# sonar.net
KiCad netlist of a schematic drawn in Altium Designer
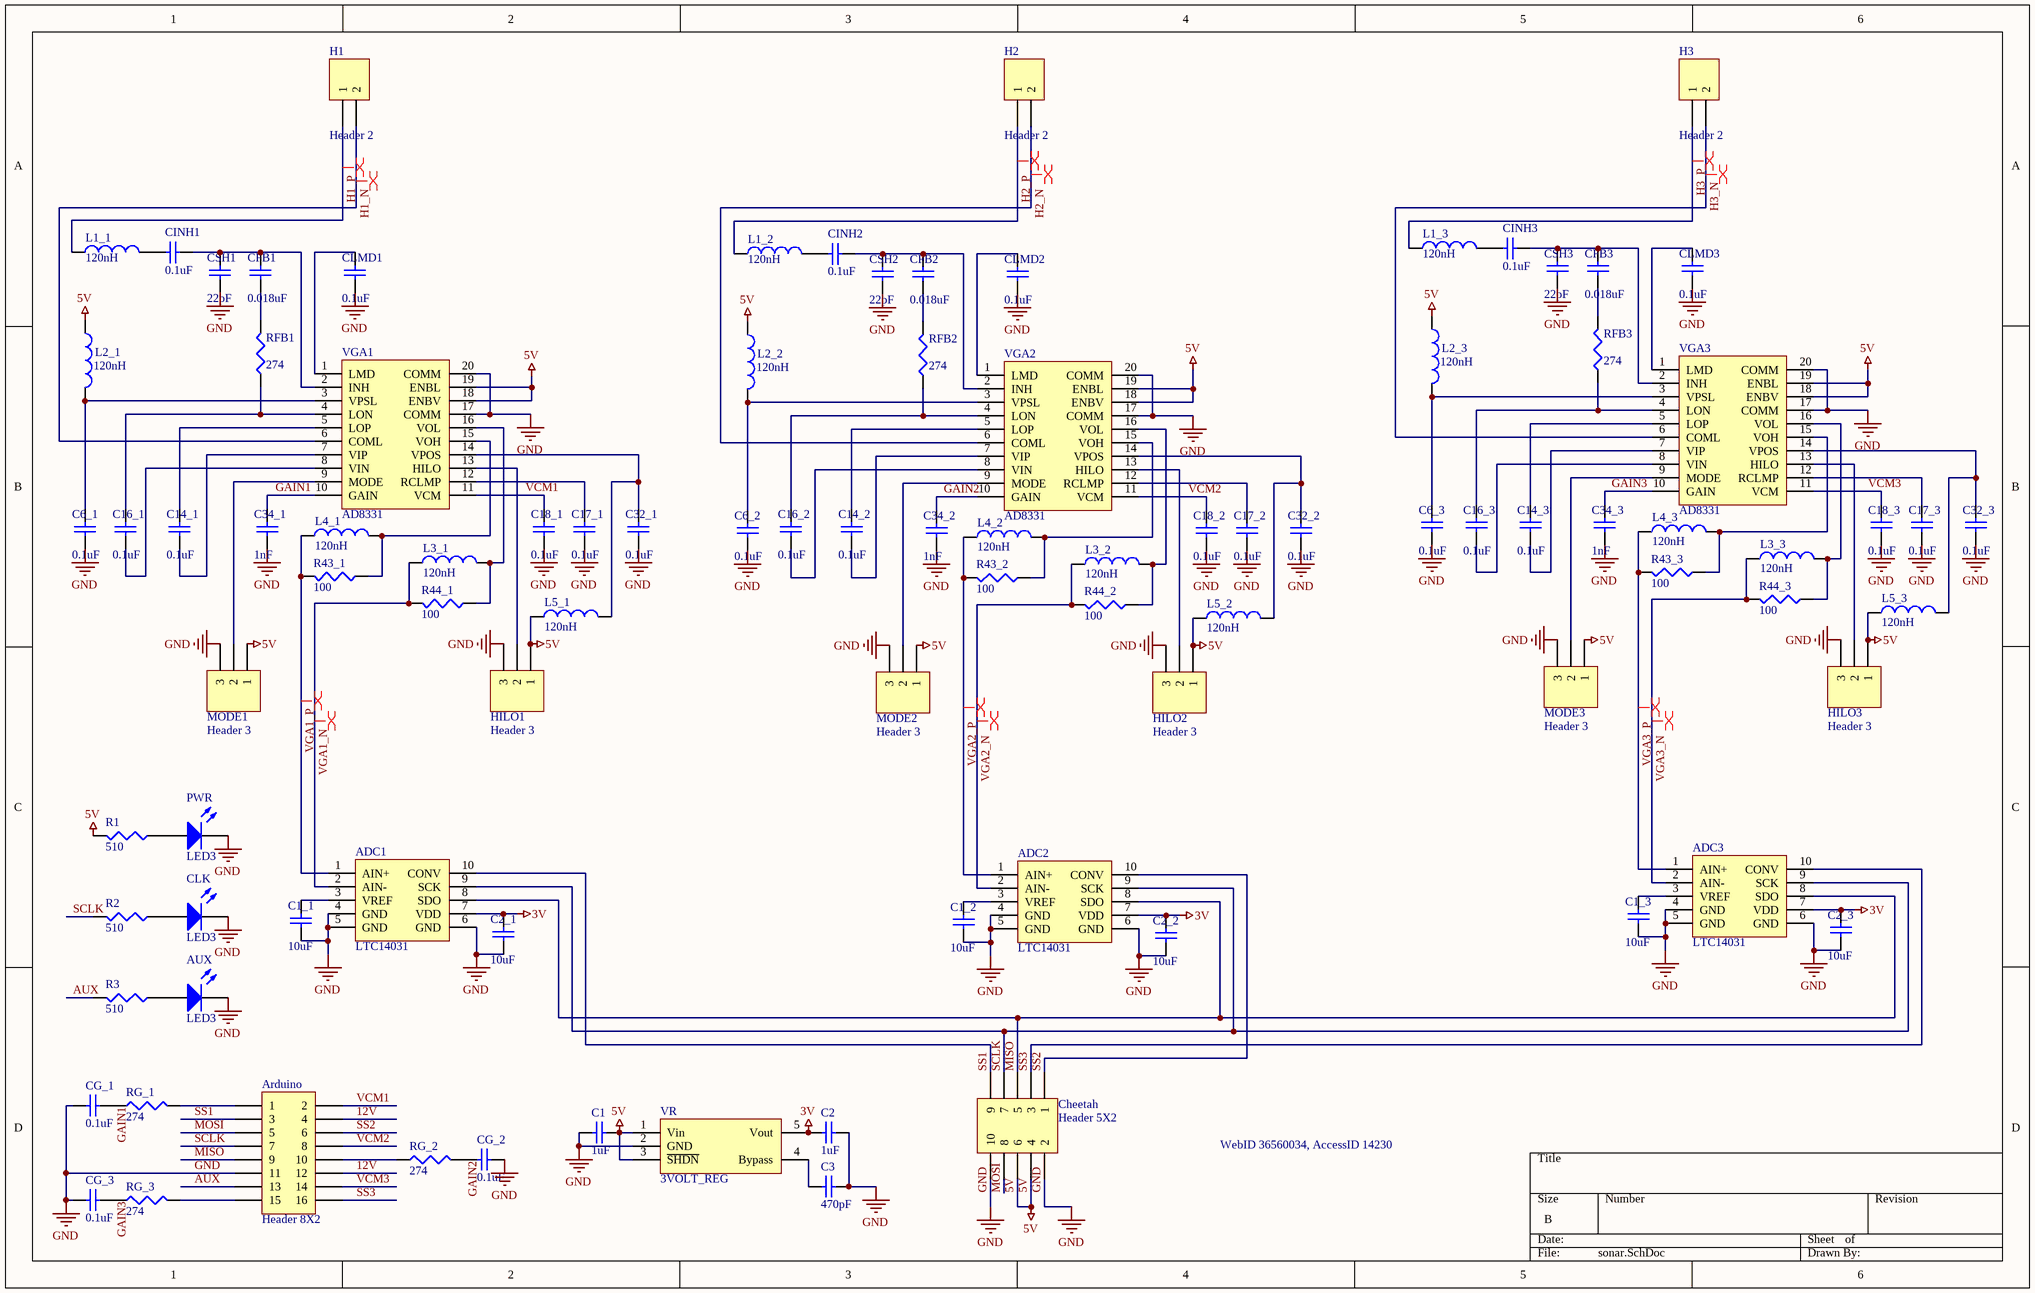
[diagram p0: sonar.SchDoc]

(export (version "E")
  (design (tool "Eeschema 10.0.6"))
  (components
    (comp (ref "ADC1") (value "LTC14031") (footprint "ADC") (libsource (lib "sonar") (part "ADC")))
    (comp (ref "ADC2") (value "LTC14031") (footprint "ADC") (libsource (lib "sonar") (part "ADC")))
    (comp (ref "ADC3") (value "LTC14031") (footprint "ADC") (libsource (lib "sonar") (part "ADC")))
    (comp (ref "Arduino")
      (value "Header 8X2")
      (footprint "HDR2X8")
      (description "Header, 8-Pin, Dual row")
      (fields (field (name "PUBLISHER") "Altium Limited"))
      (libsource (lib "Miscellaneous Connectors") (part "Header 8X2"))
    )
    (comp (ref "AUX")
      (value "LED3")
      (footprint "LED")
      (description "Typical BLUE SiC LED")
      (fields (field (name "PUBLISHER") "Altium Limited"))
      (libsource (lib "Miscellaneous Devices") (part "LED3"))
    )
    (comp (ref "C1")
      (value "1uF")
      (footprint "cap_vreg_1uf")
      (description "Capacitor")
      (fields (field (name "Comment") "Cap") (field (name "PUBLISHER") "Altium Limited"))
      (libsource (lib "Miscellaneous Devices") (part "Cap"))
    )
    (comp (ref "C1_1")
      (value "10uF")
      (footprint "cap_adc_10uf")
      (description "Capacitor")
      (fields (field (name "Comment") "Cap") (field (name "PUBLISHER") "Altium Limited"))
      (libsource (lib "Miscellaneous Devices") (part "Cap"))
    )
    (comp (ref "C1_2")
      (value "10uF")
      (footprint "cap_adc_10uf")
      (description "Capacitor")
      (fields (field (name "Comment") "Cap") (field (name "PUBLISHER") "Altium Limited"))
      (libsource (lib "Miscellaneous Devices") (part "Cap"))
    )
    (comp (ref "C1_3")
      (value "10uF")
      (footprint "cap_adc_10uf")
      (description "Capacitor")
      (fields (field (name "Comment") "Cap") (field (name "PUBLISHER") "Altium Limited"))
      (libsource (lib "Miscellaneous Devices") (part "Cap"))
    )
    (comp (ref "C2")
      (value "1uF")
      (footprint "cap_vreg_1uf")
      (description "Capacitor")
      (fields (field (name "Comment") "Cap") (field (name "PUBLISHER") "Altium Limited"))
      (libsource (lib "Miscellaneous Devices") (part "Cap"))
    )
    (comp (ref "C2_1")
      (value "10uF")
      (footprint "cap_adc_10uf")
      (description "Capacitor")
      (fields (field (name "Comment") "Cap") (field (name "PUBLISHER") "Altium Limited"))
      (libsource (lib "Miscellaneous Devices") (part "Cap"))
    )
    (comp (ref "C2_2")
      (value "10uF")
      (footprint "cap_adc_10uf")
      (description "Capacitor")
      (fields (field (name "Comment") "Cap") (field (name "PUBLISHER") "Altium Limited"))
      (libsource (lib "Miscellaneous Devices") (part "Cap"))
    )
    (comp (ref "C2_3")
      (value "10uF")
      (footprint "cap_adc_10uf")
      (description "Capacitor")
      (fields (field (name "Comment") "Cap") (field (name "PUBLISHER") "Altium Limited"))
      (libsource (lib "Miscellaneous Devices") (part "Cap"))
    )
    (comp (ref "C3")
      (value "470pF")
      (footprint "CAP_VREG_470PF")
      (description "Capacitor")
      (fields (field (name "Comment") "Cap") (field (name "PUBLISHER") "Altium Limited"))
      (libsource (lib "Miscellaneous Devices") (part "Cap"))
    )
    (comp (ref "C6_1")
      (value "0.1uF")
      (footprint "CAP_VGA_01UF")
      (description "Capacitor")
      (fields (field (name "Comment") "Cap") (field (name "PUBLISHER") "Altium Limited"))
      (libsource (lib "Miscellaneous Devices") (part "Cap"))
    )
    (comp (ref "C6_2")
      (value "0.1uF")
      (footprint "CAP_VGA_01UF")
      (description "Capacitor")
      (fields (field (name "Comment") "Cap") (field (name "PUBLISHER") "Altium Limited"))
      (libsource (lib "Miscellaneous Devices") (part "Cap"))
    )
    (comp (ref "C6_3")
      (value "0.1uF")
      (footprint "CAP_VGA_01UF")
      (description "Capacitor")
      (fields (field (name "Comment") "Cap") (field (name "PUBLISHER") "Altium Limited"))
      (libsource (lib "Miscellaneous Devices") (part "Cap"))
    )
    (comp (ref "C14_1")
      (value "0.1uF")
      (footprint "CAP_VGA_01UF")
      (description "Capacitor")
      (fields (field (name "Comment") "Cap") (field (name "PUBLISHER") "Altium Limited"))
      (libsource (lib "Miscellaneous Devices") (part "Cap"))
    )
    (comp (ref "C14_2")
      (value "0.1uF")
      (footprint "CAP_VGA_01UF")
      (description "Capacitor")
      (fields (field (name "Comment") "Cap") (field (name "PUBLISHER") "Altium Limited"))
      (libsource (lib "Miscellaneous Devices") (part "Cap"))
    )
    (comp (ref "C14_3")
      (value "0.1uF")
      (footprint "CAP_VGA_01UF")
      (description "Capacitor")
      (fields (field (name "Comment") "Cap") (field (name "PUBLISHER") "Altium Limited"))
      (libsource (lib "Miscellaneous Devices") (part "Cap"))
    )
    (comp (ref "C16_1")
      (value "0.1uF")
      (footprint "CAP_VGA_01UF")
      (description "Capacitor")
      (fields (field (name "Comment") "Cap") (field (name "PUBLISHER") "Altium Limited"))
      (libsource (lib "Miscellaneous Devices") (part "Cap"))
    )
    (comp (ref "C16_2")
      (value "0.1uF")
      (footprint "CAP_VGA_01UF")
      (description "Capacitor")
      (fields (field (name "Comment") "Cap") (field (name "PUBLISHER") "Altium Limited"))
      (libsource (lib "Miscellaneous Devices") (part "Cap"))
    )
    (comp (ref "C16_3")
      (value "0.1uF")
      (footprint "CAP_VGA_01UF")
      (description "Capacitor")
      (fields (field (name "Comment") "Cap") (field (name "PUBLISHER") "Altium Limited"))
      (libsource (lib "Miscellaneous Devices") (part "Cap"))
    )
    (comp (ref "C17_1")
      (value "0.1uF")
      (footprint "CAP_VGA_01UF")
      (description "Capacitor")
      (fields (field (name "Comment") "Cap") (field (name "PUBLISHER") "Altium Limited"))
      (libsource (lib "Miscellaneous Devices") (part "Cap"))
    )
    (comp (ref "C17_2")
      (value "0.1uF")
      (footprint "CAP_VGA_01UF")
      (description "Capacitor")
      (fields (field (name "Comment") "Cap") (field (name "PUBLISHER") "Altium Limited"))
      (libsource (lib "Miscellaneous Devices") (part "Cap"))
    )
    (comp (ref "C17_3")
      (value "0.1uF")
      (footprint "CAP_VGA_01UF")
      (description "Capacitor")
      (fields (field (name "Comment") "Cap") (field (name "PUBLISHER") "Altium Limited"))
      (libsource (lib "Miscellaneous Devices") (part "Cap"))
    )
    (comp (ref "C18_1")
      (value "0.1uF")
      (footprint "CAP_VGA_01UF")
      (description "Capacitor")
      (fields (field (name "Comment") "Cap") (field (name "PUBLISHER") "Altium Limited"))
      (libsource (lib "Miscellaneous Devices") (part "Cap"))
    )
    (comp (ref "C18_2")
      (value "0.1uF")
      (footprint "CAP_VGA_01UF")
      (description "Capacitor")
      (fields (field (name "Comment") "Cap") (field (name "PUBLISHER") "Altium Limited"))
      (libsource (lib "Miscellaneous Devices") (part "Cap"))
    )
    (comp (ref "C18_3")
      (value "0.1uF")
      (footprint "CAP_VGA_01UF")
      (description "Capacitor")
      (fields (field (name "Comment") "Cap") (field (name "PUBLISHER") "Altium Limited"))
      (libsource (lib "Miscellaneous Devices") (part "Cap"))
    )
    (comp (ref "C32_1")
      (value "0.1uF")
      (footprint "CAP_VGA_01UF")
      (description "Capacitor")
      (fields (field (name "Comment") "Cap") (field (name "PUBLISHER") "Altium Limited"))
      (libsource (lib "Miscellaneous Devices") (part "Cap"))
    )
    (comp (ref "C32_2")
      (value "0.1uF")
      (footprint "CAP_VGA_01UF")
      (description "Capacitor")
      (fields (field (name "Comment") "Cap") (field (name "PUBLISHER") "Altium Limited"))
      (libsource (lib "Miscellaneous Devices") (part "Cap"))
    )
    (comp (ref "C32_3")
      (value "0.1uF")
      (footprint "CAP_VGA_01UF")
      (description "Capacitor")
      (fields (field (name "Comment") "Cap") (field (name "PUBLISHER") "Altium Limited"))
      (libsource (lib "Miscellaneous Devices") (part "Cap"))
    )
    (comp (ref "C34_1")
      (value "1nF")
      (footprint "CAP_VGA_01UF")
      (description "Capacitor")
      (fields (field (name "Comment") "Cap") (field (name "PUBLISHER") "Altium Limited"))
      (libsource (lib "Miscellaneous Devices") (part "Cap"))
    )
    (comp (ref "C34_2")
      (value "1nF")
      (footprint "CAP_VGA_01UF")
      (description "Capacitor")
      (fields (field (name "Comment") "Cap") (field (name "PUBLISHER") "Altium Limited"))
      (libsource (lib "Miscellaneous Devices") (part "Cap"))
    )
    (comp (ref "C34_3")
      (value "1nF")
      (footprint "CAP_VGA_01UF")
      (description "Capacitor")
      (fields (field (name "Comment") "Cap") (field (name "PUBLISHER") "Altium Limited"))
      (libsource (lib "Miscellaneous Devices") (part "Cap"))
    )
    (comp (ref "CFB1")
      (value "0.018uF")
      (footprint "CAP_VGA_01UF")
      (description "Capacitor")
      (fields (field (name "Comment") "Cap") (field (name "PUBLISHER") "Altium Limited"))
      (libsource (lib "Miscellaneous Devices") (part "Cap"))
    )
    (comp (ref "CFB2")
      (value "0.018uF")
      (footprint "CAP_VGA_01UF")
      (description "Capacitor")
      (fields (field (name "Comment") "Cap") (field (name "PUBLISHER") "Altium Limited"))
      (libsource (lib "Miscellaneous Devices") (part "Cap"))
    )
    (comp (ref "CFB3")
      (value "0.018uF")
      (footprint "CAP_VGA_01UF")
      (description "Capacitor")
      (fields (field (name "Comment") "Cap") (field (name "PUBLISHER") "Altium Limited"))
      (libsource (lib "Miscellaneous Devices") (part "Cap"))
    )
    (comp (ref "CG_1")
      (value "0.1uF")
      (footprint "CAP_VGA_01UF")
      (description "Capacitor")
      (fields (field (name "Comment") "Cap") (field (name "PUBLISHER") "Altium Limited"))
      (libsource (lib "Miscellaneous Devices") (part "Cap"))
    )
    (comp (ref "CG_2")
      (value "0.1uF")
      (footprint "CAP_VGA_01UF")
      (description "Capacitor")
      (fields (field (name "Comment") "Cap") (field (name "PUBLISHER") "Altium Limited"))
      (libsource (lib "Miscellaneous Devices") (part "Cap"))
    )
    (comp (ref "CG_3")
      (value "0.1uF")
      (footprint "CAP_VGA_01UF")
      (description "Capacitor")
      (fields (field (name "Comment") "Cap") (field (name "PUBLISHER") "Altium Limited"))
      (libsource (lib "Miscellaneous Devices") (part "Cap"))
    )
    (comp (ref "Cheetah")
      (value "Header 5X2")
      (footprint "HDR2X5")
      (description "Header, 5-Pin, Dual row")
      (fields (field (name "PUBLISHER") "Altium Limited"))
      (libsource (lib "Miscellaneous Connectors") (part "Header 5X2"))
    )
    (comp (ref "CINH1")
      (value "0.1uF")
      (footprint "CAP_VGA_01UF")
      (description "Capacitor")
      (fields (field (name "Comment") "Cap") (field (name "PUBLISHER") "Altium Limited"))
      (libsource (lib "Miscellaneous Devices") (part "Cap"))
    )
    (comp (ref "CINH2")
      (value "0.1uF")
      (footprint "CAP_VGA_01UF")
      (description "Capacitor")
      (fields (field (name "Comment") "Cap") (field (name "PUBLISHER") "Altium Limited"))
      (libsource (lib "Miscellaneous Devices") (part "Cap"))
    )
    (comp (ref "CINH3")
      (value "0.1uF")
      (footprint "CAP_VGA_01UF")
      (description "Capacitor")
      (fields (field (name "Comment") "Cap") (field (name "PUBLISHER") "Altium Limited"))
      (libsource (lib "Miscellaneous Devices") (part "Cap"))
    )
    (comp (ref "CLK")
      (value "LED3")
      (footprint "LED")
      (description "Typical BLUE SiC LED")
      (fields (field (name "PUBLISHER") "Altium Limited"))
      (libsource (lib "Miscellaneous Devices") (part "LED3"))
    )
    (comp (ref "CLMD1")
      (value "0.1uF")
      (footprint "CAP_VGA_01UF")
      (description "Capacitor")
      (fields (field (name "Comment") "Cap") (field (name "PUBLISHER") "Altium Limited"))
      (libsource (lib "Miscellaneous Devices") (part "Cap"))
    )
    (comp (ref "CLMD2")
      (value "0.1uF")
      (footprint "CAP_VGA_01UF")
      (description "Capacitor")
      (fields (field (name "Comment") "Cap") (field (name "PUBLISHER") "Altium Limited"))
      (libsource (lib "Miscellaneous Devices") (part "Cap"))
    )
    (comp (ref "CLMD3")
      (value "0.1uF")
      (footprint "CAP_VGA_01UF")
      (description "Capacitor")
      (fields (field (name "Comment") "Cap") (field (name "PUBLISHER") "Altium Limited"))
      (libsource (lib "Miscellaneous Devices") (part "Cap"))
    )
    (comp (ref "CSH1")
      (value "22pF")
      (footprint "CAP_VGA_01UF")
      (description "Capacitor")
      (fields (field (name "Comment") "Cap") (field (name "PUBLISHER") "Altium Limited"))
      (libsource (lib "Miscellaneous Devices") (part "Cap"))
    )
    (comp (ref "CSH2")
      (value "22pF")
      (footprint "CAP_VGA_01UF")
      (description "Capacitor")
      (fields (field (name "Comment") "Cap") (field (name "PUBLISHER") "Altium Limited"))
      (libsource (lib "Miscellaneous Devices") (part "Cap"))
    )
    (comp (ref "CSH3")
      (value "22pF")
      (footprint "CAP_VGA_01UF")
      (description "Capacitor")
      (fields (field (name "Comment") "Cap") (field (name "PUBLISHER") "Altium Limited"))
      (libsource (lib "Miscellaneous Devices") (part "Cap"))
    )
    (comp (ref "H1")
      (value "Header 2")
      (footprint "bnc")
      (description "Header, 2-Pin")
      (fields (field (name "PUBLISHER") "Altium Limited"))
      (libsource (lib "Miscellaneous Connectors") (part "Header 2"))
    )
    (comp (ref "H2")
      (value "Header 2")
      (footprint "bnc")
      (description "Header, 2-Pin")
      (fields (field (name "PUBLISHER") "Altium Limited"))
      (libsource (lib "Miscellaneous Connectors") (part "Header 2"))
    )
    (comp (ref "H3")
      (value "Header 2")
      (footprint "bnc")
      (description "Header, 2-Pin")
      (fields (field (name "PUBLISHER") "Altium Limited"))
      (libsource (lib "Miscellaneous Connectors") (part "Header 2"))
    )
    (comp (ref "HILO1")
      (value "Header 3")
      (footprint "HDR1X3")
      (description "Header, 3-Pin")
      (fields (field (name "PUBLISHER") "Altium Limited"))
      (libsource (lib "Miscellaneous Connectors") (part "Header 3"))
    )
    (comp (ref "HILO2")
      (value "Header 3")
      (footprint "HDR1X3")
      (description "Header, 3-Pin")
      (fields (field (name "PUBLISHER") "Altium Limited"))
      (libsource (lib "Miscellaneous Connectors") (part "Header 3"))
    )
    (comp (ref "HILO3")
      (value "Header 3")
      (footprint "HDR1X3")
      (description "Header, 3-Pin")
      (fields (field (name "PUBLISHER") "Altium Limited"))
      (libsource (lib "Miscellaneous Connectors") (part "Header 3"))
    )
    (comp (ref "L1_1")
      (value "120nH")
      (footprint "ind_vga_120nh")
      (description "Inductor")
      (fields (field (name "Comment") "FB Inductor") (field (name "PUBLISHER") "Altium Limited"))
      (libsource (lib "Miscellaneous Devices") (part "Inductor"))
    )
    (comp (ref "L1_2")
      (value "120nH")
      (footprint "ind_vga_120nh")
      (description "Inductor")
      (fields (field (name "Comment") "FB Inductor") (field (name "PUBLISHER") "Altium Limited"))
      (libsource (lib "Miscellaneous Devices") (part "Inductor"))
    )
    (comp (ref "L1_3")
      (value "120nH")
      (footprint "ind_vga_120nh")
      (description "Inductor")
      (fields (field (name "Comment") "FB Inductor") (field (name "PUBLISHER") "Altium Limited"))
      (libsource (lib "Miscellaneous Devices") (part "Inductor"))
    )
    (comp (ref "L2_1")
      (value "120nH")
      (footprint "ind_vga_120nh")
      (description "Inductor")
      (fields (field (name "Comment") "FB Inductor") (field (name "PUBLISHER") "Altium Limited"))
      (libsource (lib "Miscellaneous Devices") (part "Inductor"))
    )
    (comp (ref "L2_2")
      (value "120nH")
      (footprint "ind_vga_120nh")
      (description "Inductor")
      (fields (field (name "Comment") "FB Inductor") (field (name "PUBLISHER") "Altium Limited"))
      (libsource (lib "Miscellaneous Devices") (part "Inductor"))
    )
    (comp (ref "L2_3")
      (value "120nH")
      (footprint "ind_vga_120nh")
      (description "Inductor")
      (fields (field (name "Comment") "FB Inductor") (field (name "PUBLISHER") "Altium Limited"))
      (libsource (lib "Miscellaneous Devices") (part "Inductor"))
    )
    (comp (ref "L3_1")
      (value "120nH")
      (footprint "ind_vga_120nh")
      (description "Inductor")
      (fields (field (name "Comment") "FB Inductor") (field (name "PUBLISHER") "Altium Limited"))
      (libsource (lib "Miscellaneous Devices") (part "Inductor"))
    )
    (comp (ref "L3_2")
      (value "120nH")
      (footprint "ind_vga_120nh")
      (description "Inductor")
      (fields (field (name "Comment") "FB Inductor") (field (name "PUBLISHER") "Altium Limited"))
      (libsource (lib "Miscellaneous Devices") (part "Inductor"))
    )
    (comp (ref "L3_3")
      (value "120nH")
      (footprint "ind_vga_120nh")
      (description "Inductor")
      (fields (field (name "Comment") "FB Inductor") (field (name "PUBLISHER") "Altium Limited"))
      (libsource (lib "Miscellaneous Devices") (part "Inductor"))
    )
    (comp (ref "L4_1")
      (value "120nH")
      (footprint "ind_vga_120nh")
      (description "Inductor")
      (fields (field (name "Comment") "FB Inductor") (field (name "PUBLISHER") "Altium Limited"))
      (libsource (lib "Miscellaneous Devices") (part "Inductor"))
    )
    (comp (ref "L4_2")
      (value "120nH")
      (footprint "ind_vga_120nh")
      (description "Inductor")
      (fields (field (name "Comment") "FB Inductor") (field (name "PUBLISHER") "Altium Limited"))
      (libsource (lib "Miscellaneous Devices") (part "Inductor"))
    )
    (comp (ref "L4_3")
      (value "120nH")
      (footprint "ind_vga_120nh")
      (description "Inductor")
      (fields (field (name "Comment") "FB Inductor") (field (name "PUBLISHER") "Altium Limited"))
      (libsource (lib "Miscellaneous Devices") (part "Inductor"))
    )
    (comp (ref "L5_1")
      (value "120nH")
      (footprint "ind_vga_120nh")
      (description "Inductor")
      (fields (field (name "Comment") "FB Inductor") (field (name "PUBLISHER") "Altium Limited"))
      (libsource (lib "Miscellaneous Devices") (part "Inductor"))
    )
    (comp (ref "L5_2")
      (value "120nH")
      (footprint "ind_vga_120nh")
      (description "Inductor")
      (fields (field (name "Comment") "FB Inductor") (field (name "PUBLISHER") "Altium Limited"))
      (libsource (lib "Miscellaneous Devices") (part "Inductor"))
    )
    (comp (ref "L5_3")
      (value "120nH")
      (footprint "ind_vga_120nh")
      (description "Inductor")
      (fields (field (name "Comment") "FB Inductor") (field (name "PUBLISHER") "Altium Limited"))
      (libsource (lib "Miscellaneous Devices") (part "Inductor"))
    )
    (comp (ref "MODE1")
      (value "Header 3")
      (footprint "HDR1X3")
      (description "Header, 3-Pin")
      (fields (field (name "PUBLISHER") "Altium Limited"))
      (libsource (lib "Miscellaneous Connectors") (part "Header 3"))
    )
    (comp (ref "MODE2")
      (value "Header 3")
      (footprint "HDR1X3")
      (description "Header, 3-Pin")
      (fields (field (name "PUBLISHER") "Altium Limited"))
      (libsource (lib "Miscellaneous Connectors") (part "Header 3"))
    )
    (comp (ref "MODE3")
      (value "Header 3")
      (footprint "HDR1X3")
      (description "Header, 3-Pin")
      (fields (field (name "PUBLISHER") "Altium Limited"))
      (libsource (lib "Miscellaneous Connectors") (part "Header 3"))
    )
    (comp (ref "PWR")
      (value "LED3")
      (footprint "LED")
      (description "Typical BLUE SiC LED")
      (fields (field (name "PUBLISHER") "Altium Limited"))
      (libsource (lib "Miscellaneous Devices") (part "LED3"))
    )
    (comp (ref "R1")
      (value "510")
      (footprint "res_vga_274")
      (description "Resistor")
      (fields (field (name "Comment") "Res3") (field (name "PUBLISHER") "Altium Limited"))
      (libsource (lib "Miscellaneous Devices") (part "Res3"))
    )
    (comp (ref "R2")
      (value "510")
      (footprint "res_vga_274")
      (description "Resistor")
      (fields (field (name "Comment") "Res3") (field (name "PUBLISHER") "Altium Limited"))
      (libsource (lib "Miscellaneous Devices") (part "Res3"))
    )
    (comp (ref "R3")
      (value "510")
      (footprint "res_vga_274")
      (description "Resistor")
      (fields (field (name "Comment") "Res3") (field (name "PUBLISHER") "Altium Limited"))
      (libsource (lib "Miscellaneous Devices") (part "Res3"))
    )
    (comp (ref "R43_1")
      (value "100")
      (footprint "res_vga_274")
      (description "Resistor")
      (fields (field (name "Comment") "Res3") (field (name "PUBLISHER") "Altium Limited"))
      (libsource (lib "Miscellaneous Devices") (part "Res3"))
    )
    (comp (ref "R43_2")
      (value "100")
      (footprint "res_vga_274")
      (description "Resistor")
      (fields (field (name "Comment") "Res3") (field (name "PUBLISHER") "Altium Limited"))
      (libsource (lib "Miscellaneous Devices") (part "Res3"))
    )
    (comp (ref "R43_3")
      (value "100")
      (footprint "res_vga_274")
      (description "Resistor")
      (fields (field (name "Comment") "Res3") (field (name "PUBLISHER") "Altium Limited"))
      (libsource (lib "Miscellaneous Devices") (part "Res3"))
    )
    (comp (ref "R44_1")
      (value "100")
      (footprint "res_vga_274")
      (description "Resistor")
      (fields (field (name "Comment") "Res3") (field (name "PUBLISHER") "Altium Limited"))
      (libsource (lib "Miscellaneous Devices") (part "Res3"))
    )
    (comp (ref "R44_2")
      (value "100")
      (footprint "res_vga_274")
      (description "Resistor")
      (fields (field (name "Comment") "Res3") (field (name "PUBLISHER") "Altium Limited"))
      (libsource (lib "Miscellaneous Devices") (part "Res3"))
    )
    (comp (ref "R44_3")
      (value "100")
      (footprint "res_vga_274")
      (description "Resistor")
      (fields (field (name "Comment") "Res3") (field (name "PUBLISHER") "Altium Limited"))
      (libsource (lib "Miscellaneous Devices") (part "Res3"))
    )
    (comp (ref "RFB1")
      (value "274")
      (footprint "res_vga_274")
      (description "Resistor")
      (fields (field (name "Comment") "Res3") (field (name "PUBLISHER") "Altium Limited"))
      (libsource (lib "Miscellaneous Devices") (part "Res3"))
    )
    (comp (ref "RFB2")
      (value "274")
      (footprint "res_vga_274")
      (description "Resistor")
      (fields (field (name "Comment") "Res3") (field (name "PUBLISHER") "Altium Limited"))
      (libsource (lib "Miscellaneous Devices") (part "Res3"))
    )
    (comp (ref "RFB3")
      (value "274")
      (footprint "res_vga_274")
      (description "Resistor")
      (fields (field (name "Comment") "Res3") (field (name "PUBLISHER") "Altium Limited"))
      (libsource (lib "Miscellaneous Devices") (part "Res3"))
    )
    (comp (ref "RG_1")
      (value "274")
      (footprint "res_vga_274")
      (description "Resistor")
      (fields (field (name "Comment") "Res3") (field (name "PUBLISHER") "Altium Limited"))
      (libsource (lib "Miscellaneous Devices") (part "Res3"))
    )
    (comp (ref "RG_2")
      (value "274")
      (footprint "res_vga_274")
      (description "Resistor")
      (fields (field (name "Comment") "Res3") (field (name "PUBLISHER") "Altium Limited"))
      (libsource (lib "Miscellaneous Devices") (part "Res3"))
    )
    (comp (ref "RG_3")
      (value "274")
      (footprint "res_vga_274")
      (description "Resistor")
      (fields (field (name "Comment") "Res3") (field (name "PUBLISHER") "Altium Limited"))
      (libsource (lib "Miscellaneous Devices") (part "Res3"))
    )
    (comp (ref "VGA1") (value "AD8331") (footprint "VGA") (libsource (lib "sonar") (part "VGA")))
    (comp (ref "VGA2") (value "AD8331") (footprint "VGA") (libsource (lib "sonar") (part "VGA")))
    (comp (ref "VGA3") (value "AD8331") (footprint "VGA") (libsource (lib "sonar") (part "VGA")))
    (comp (ref "VR") (value "3VOLT_REG") (footprint "3VOLT_REG") (libsource (lib "sonar") (part "3VOLT_REG")))
  )
  (nets
    (net (code "1") (name "/12V") (class "Default")
      (node (ref "Arduino") (pin "12") (pinfunction "12_12") (pintype "passive"))
      (node (ref "Arduino") (pin "4") (pinfunction "4_4") (pintype "passive"))
    )
    (net (code "2") (name "/AUX") (class "Default")
      (node (ref "Arduino") (pin "13") (pinfunction "13_13") (pintype "passive"))
      (node (ref "R3") (pin "2") (pinfunction "2_2") (pintype "passive"))
    )
    (net (code "3") (name "/GAIN1") (class "Default")
      (node (ref "C34_1") (pin "2") (pinfunction "2_2") (pintype "passive"))
      (node (ref "CG_1") (pin "2") (pinfunction "2_2") (pintype "passive"))
      (node (ref "RG_1") (pin "1") (pinfunction "1_1") (pintype "passive"))
      (node (ref "VGA1") (pin "10") (pinfunction "GAIN_10") (pintype "power_in"))
    )
    (net (code "4") (name "/GAIN2") (class "Default")
      (node (ref "C34_2") (pin "2") (pinfunction "2_2") (pintype "passive"))
      (node (ref "CG_2") (pin "1") (pinfunction "1_1") (pintype "passive"))
      (node (ref "RG_2") (pin "2") (pinfunction "2_2") (pintype "passive"))
      (node (ref "VGA2") (pin "10") (pinfunction "GAIN_10") (pintype "power_in"))
    )
    (net (code "5") (name "/GAIN3") (class "Default")
      (node (ref "C34_3") (pin "2") (pinfunction "2_2") (pintype "passive"))
      (node (ref "CG_3") (pin "1") (pinfunction "1_1") (pintype "passive"))
      (node (ref "RG_3") (pin "1") (pinfunction "1_1") (pintype "passive"))
      (node (ref "VGA3") (pin "10") (pinfunction "GAIN_10") (pintype "power_in"))
    )
    (net (code "6") (name "/H1_N") (class "Default")
      (node (ref "H1") (pin "2") (pinfunction "2_2") (pintype "passive"))
      (node (ref "VGA1") (pin "6") (pinfunction "COML_6") (pintype "power_in"))
    )
    (net (code "7") (name "/H1_P") (class "Default")
      (node (ref "H1") (pin "1") (pinfunction "1_1") (pintype "passive"))
      (node (ref "L1_1") (pin "1") (pinfunction "1_1") (pintype "passive"))
    )
    (net (code "8") (name "/H2_N") (class "Default")
      (node (ref "H2") (pin "2") (pinfunction "2_2") (pintype "passive"))
      (node (ref "VGA2") (pin "6") (pinfunction "COML_6") (pintype "power_in"))
    )
    (net (code "9") (name "/H2_P") (class "Default")
      (node (ref "H2") (pin "1") (pinfunction "1_1") (pintype "passive"))
      (node (ref "L1_2") (pin "1") (pinfunction "1_1") (pintype "passive"))
    )
    (net (code "10") (name "/H3_N") (class "Default")
      (node (ref "H3") (pin "2") (pinfunction "2_2") (pintype "passive"))
      (node (ref "VGA3") (pin "6") (pinfunction "COML_6") (pintype "power_in"))
    )
    (net (code "11") (name "/H3_P") (class "Default")
      (node (ref "H3") (pin "1") (pinfunction "1_1") (pintype "passive"))
      (node (ref "L1_3") (pin "1") (pinfunction "1_1") (pintype "passive"))
    )
    (net (code "12") (name "/MISO") (class "Default")
      (node (ref "ADC1") (pin "8") (pinfunction "SDO_8") (pintype "power_in"))
      (node (ref "ADC2") (pin "8") (pinfunction "SDO_8") (pintype "power_in"))
      (node (ref "ADC3") (pin "8") (pinfunction "SDO_8") (pintype "power_in"))
      (node (ref "Arduino") (pin "9") (pinfunction "9_9") (pintype "passive"))
      (node (ref "Cheetah") (pin "5") (pinfunction "5_5") (pintype "passive"))
    )
    (net (code "13") (name "/MOSI") (class "Default")
      (node (ref "Arduino") (pin "5") (pinfunction "5_5") (pintype "passive"))
      (node (ref "Cheetah") (pin "8") (pinfunction "8_8") (pintype "passive"))
    )
    (net (code "14") (name "/SCLK") (class "Default")
      (node (ref "ADC1") (pin "9") (pinfunction "SCK_9") (pintype "power_in"))
      (node (ref "ADC2") (pin "9") (pinfunction "SCK_9") (pintype "power_in"))
      (node (ref "ADC3") (pin "9") (pinfunction "SCK_9") (pintype "power_in"))
      (node (ref "Arduino") (pin "7") (pinfunction "7_7") (pintype "passive"))
      (node (ref "Cheetah") (pin "7") (pinfunction "7_7") (pintype "passive"))
      (node (ref "R2") (pin "2") (pinfunction "2_2") (pintype "passive"))
    )
    (net (code "15") (name "/SS1") (class "Default")
      (node (ref "ADC1") (pin "10") (pinfunction "CONV_10") (pintype "power_in"))
      (node (ref "Arduino") (pin "3") (pinfunction "3_3") (pintype "passive"))
      (node (ref "Cheetah") (pin "9") (pinfunction "9_9") (pintype "passive"))
    )
    (net (code "16") (name "/SS2") (class "Default")
      (node (ref "ADC2") (pin "10") (pinfunction "CONV_10") (pintype "power_in"))
      (node (ref "Arduino") (pin "6") (pinfunction "6_6") (pintype "passive"))
      (node (ref "Cheetah") (pin "1") (pinfunction "1_1") (pintype "passive"))
    )
    (net (code "17") (name "/SS3") (class "Default")
      (node (ref "ADC3") (pin "10") (pinfunction "CONV_10") (pintype "power_in"))
      (node (ref "Arduino") (pin "16") (pinfunction "16_16") (pintype "passive"))
      (node (ref "Cheetah") (pin "3") (pinfunction "3_3") (pintype "passive"))
    )
    (net (code "18") (name "/VCM1") (class "Default")
      (node (ref "Arduino") (pin "2") (pinfunction "2_2") (pintype "passive"))
      (node (ref "C18_1") (pin "2") (pinfunction "2_2") (pintype "passive"))
      (node (ref "VGA1") (pin "11") (pinfunction "VCM_11") (pintype "power_in"))
    )
    (net (code "19") (name "/VCM2") (class "Default")
      (node (ref "Arduino") (pin "8") (pinfunction "8_8") (pintype "passive"))
      (node (ref "C18_2") (pin "2") (pinfunction "2_2") (pintype "passive"))
      (node (ref "VGA2") (pin "11") (pinfunction "VCM_11") (pintype "power_in"))
    )
    (net (code "20") (name "/VCM3") (class "Default")
      (node (ref "Arduino") (pin "14") (pinfunction "14_14") (pintype "passive"))
      (node (ref "C18_3") (pin "2") (pinfunction "2_2") (pintype "passive"))
      (node (ref "VGA3") (pin "11") (pinfunction "VCM_11") (pintype "power_in"))
    )
    (net (code "21") (name "/VGA1_N") (class "Default")
      (node (ref "ADC1") (pin "2") (pinfunction "AIN-_2") (pintype "power_in"))
      (node (ref "L3_1") (pin "1") (pinfunction "1_1") (pintype "passive"))
      (node (ref "R44_1") (pin "2") (pinfunction "2_2") (pintype "passive"))
    )
    (net (code "22") (name "/VGA1_P") (class "Default")
      (node (ref "ADC1") (pin "1") (pinfunction "AIN+_1") (pintype "power_in"))
      (node (ref "L4_1") (pin "1") (pinfunction "1_1") (pintype "passive"))
      (node (ref "R43_1") (pin "2") (pinfunction "2_2") (pintype "passive"))
    )
    (net (code "23") (name "/VGA2_N") (class "Default")
      (node (ref "ADC2") (pin "2") (pinfunction "AIN-_2") (pintype "power_in"))
      (node (ref "L3_2") (pin "1") (pinfunction "1_1") (pintype "passive"))
      (node (ref "R44_2") (pin "2") (pinfunction "2_2") (pintype "passive"))
    )
    (net (code "24") (name "/VGA2_P") (class "Default")
      (node (ref "ADC2") (pin "1") (pinfunction "AIN+_1") (pintype "power_in"))
      (node (ref "L4_2") (pin "1") (pinfunction "1_1") (pintype "passive"))
      (node (ref "R43_2") (pin "2") (pinfunction "2_2") (pintype "passive"))
    )
    (net (code "25") (name "/VGA3_N") (class "Default")
      (node (ref "ADC3") (pin "2") (pinfunction "AIN-_2") (pintype "power_in"))
      (node (ref "L3_3") (pin "1") (pinfunction "1_1") (pintype "passive"))
      (node (ref "R44_3") (pin "2") (pinfunction "2_2") (pintype "passive"))
    )
    (net (code "26") (name "/VGA3_P") (class "Default")
      (node (ref "ADC3") (pin "1") (pinfunction "AIN+_1") (pintype "power_in"))
      (node (ref "L4_3") (pin "1") (pinfunction "1_1") (pintype "passive"))
      (node (ref "R43_3") (pin "2") (pinfunction "2_2") (pintype "passive"))
    )
    (net (code "27") (name "3V") (class "Default")
      (node (ref "ADC1") (pin "7") (pinfunction "VDD_7") (pintype "power_in"))
      (node (ref "ADC2") (pin "7") (pinfunction "VDD_7") (pintype "power_in"))
      (node (ref "ADC3") (pin "7") (pinfunction "VDD_7") (pintype "power_in"))
      (node (ref "C2") (pin "2") (pinfunction "2_2") (pintype "passive"))
      (node (ref "C2_1") (pin "2") (pinfunction "2_2") (pintype "passive"))
      (node (ref "C2_2") (pin "2") (pinfunction "2_2") (pintype "passive"))
      (node (ref "C2_3") (pin "2") (pinfunction "2_2") (pintype "passive"))
      (node (ref "VR") (pin "5") (pinfunction "Vout_5") (pintype "power_in"))
    )
    (net (code "28") (name "5V") (class "Default")
      (node (ref "C1") (pin "1") (pinfunction "1_1") (pintype "passive"))
      (node (ref "Cheetah") (pin "4") (pinfunction "4_4") (pintype "passive"))
      (node (ref "Cheetah") (pin "6") (pinfunction "6_6") (pintype "passive"))
      (node (ref "HILO1") (pin "1") (pinfunction "1_1") (pintype "passive"))
      (node (ref "HILO2") (pin "1") (pinfunction "1_1") (pintype "passive"))
      (node (ref "HILO3") (pin "1") (pinfunction "1_1") (pintype "passive"))
      (node (ref "L2_1") (pin "1") (pinfunction "1_1") (pintype "passive"))
      (node (ref "L2_2") (pin "1") (pinfunction "1_1") (pintype "passive"))
      (node (ref "L2_3") (pin "1") (pinfunction "1_1") (pintype "passive"))
      (node (ref "L5_1") (pin "1") (pinfunction "1_1") (pintype "passive"))
      (node (ref "L5_2") (pin "1") (pinfunction "1_1") (pintype "passive"))
      (node (ref "L5_3") (pin "1") (pinfunction "1_1") (pintype "passive"))
      (node (ref "MODE1") (pin "1") (pinfunction "1_1") (pintype "passive"))
      (node (ref "MODE2") (pin "1") (pinfunction "1_1") (pintype "passive"))
      (node (ref "MODE3") (pin "1") (pinfunction "1_1") (pintype "passive"))
      (node (ref "R1") (pin "2") (pinfunction "2_2") (pintype "passive"))
      (node (ref "VGA1") (pin "18") (pinfunction "ENBV_18") (pintype "power_in"))
      (node (ref "VGA1") (pin "19") (pinfunction "ENBL_19") (pintype "power_in"))
      (node (ref "VGA2") (pin "18") (pinfunction "ENBV_18") (pintype "power_in"))
      (node (ref "VGA2") (pin "19") (pinfunction "ENBL_19") (pintype "power_in"))
      (node (ref "VGA3") (pin "18") (pinfunction "ENBV_18") (pintype "power_in"))
      (node (ref "VGA3") (pin "19") (pinfunction "ENBL_19") (pintype "power_in"))
      (node (ref "VR") (pin "1") (pinfunction "Vin_1") (pintype "power_in"))
      (node (ref "VR") (pin "3") (pinfunction "~{SHDN}_3") (pintype "power_in"))
    )
    (net (code "29") (name "GND") (class "Default")
      (node (ref "ADC1") (pin "4") (pinfunction "GND_4") (pintype "power_in"))
      (node (ref "ADC1") (pin "5") (pinfunction "GND_5") (pintype "power_in"))
      (node (ref "ADC1") (pin "6") (pinfunction "GND_6") (pintype "power_in"))
      (node (ref "ADC2") (pin "4") (pinfunction "GND_4") (pintype "power_in"))
      (node (ref "ADC2") (pin "5") (pinfunction "GND_5") (pintype "power_in"))
      (node (ref "ADC2") (pin "6") (pinfunction "GND_6") (pintype "power_in"))
      (node (ref "ADC3") (pin "4") (pinfunction "GND_4") (pintype "power_in"))
      (node (ref "ADC3") (pin "5") (pinfunction "GND_5") (pintype "power_in"))
      (node (ref "ADC3") (pin "6") (pinfunction "GND_6") (pintype "power_in"))
      (node (ref "AUX") (pin "2") (pinfunction "K_2") (pintype "passive"))
      (node (ref "Arduino") (pin "11") (pinfunction "11_11") (pintype "passive"))
      (node (ref "C1") (pin "2") (pinfunction "2_2") (pintype "passive"))
      (node (ref "C17_1") (pin "1") (pinfunction "1_1") (pintype "passive"))
      (node (ref "C17_2") (pin "1") (pinfunction "1_1") (pintype "passive"))
      (node (ref "C17_3") (pin "1") (pinfunction "1_1") (pintype "passive"))
      (node (ref "C18_1") (pin "1") (pinfunction "1_1") (pintype "passive"))
      (node (ref "C18_2") (pin "1") (pinfunction "1_1") (pintype "passive"))
      (node (ref "C18_3") (pin "1") (pinfunction "1_1") (pintype "passive"))
      (node (ref "C1_1") (pin "1") (pinfunction "1_1") (pintype "passive"))
      (node (ref "C1_2") (pin "1") (pinfunction "1_1") (pintype "passive"))
      (node (ref "C1_3") (pin "1") (pinfunction "1_1") (pintype "passive"))
      (node (ref "C2") (pin "1") (pinfunction "1_1") (pintype "passive"))
      (node (ref "C2_1") (pin "1") (pinfunction "1_1") (pintype "passive"))
      (node (ref "C2_2") (pin "1") (pinfunction "1_1") (pintype "passive"))
      (node (ref "C2_3") (pin "1") (pinfunction "1_1") (pintype "passive"))
      (node (ref "C3") (pin "1") (pinfunction "1_1") (pintype "passive"))
      (node (ref "C32_1") (pin "1") (pinfunction "1_1") (pintype "passive"))
      (node (ref "C32_2") (pin "1") (pinfunction "1_1") (pintype "passive"))
      (node (ref "C32_3") (pin "1") (pinfunction "1_1") (pintype "passive"))
      (node (ref "C34_1") (pin "1") (pinfunction "1_1") (pintype "passive"))
      (node (ref "C34_2") (pin "1") (pinfunction "1_1") (pintype "passive"))
      (node (ref "C34_3") (pin "1") (pinfunction "1_1") (pintype "passive"))
      (node (ref "C6_1") (pin "1") (pinfunction "1_1") (pintype "passive"))
      (node (ref "C6_2") (pin "1") (pinfunction "1_1") (pintype "passive"))
      (node (ref "C6_3") (pin "1") (pinfunction "1_1") (pintype "passive"))
      (node (ref "CG_1") (pin "1") (pinfunction "1_1") (pintype "passive"))
      (node (ref "CG_2") (pin "2") (pinfunction "2_2") (pintype "passive"))
      (node (ref "CG_3") (pin "2") (pinfunction "2_2") (pintype "passive"))
      (node (ref "CLK") (pin "2") (pinfunction "K_2") (pintype "passive"))
      (node (ref "CLMD1") (pin "1") (pinfunction "1_1") (pintype "passive"))
      (node (ref "CLMD2") (pin "1") (pinfunction "1_1") (pintype "passive"))
      (node (ref "CLMD3") (pin "1") (pinfunction "1_1") (pintype "passive"))
      (node (ref "CSH1") (pin "1") (pinfunction "1_1") (pintype "passive"))
      (node (ref "CSH2") (pin "1") (pinfunction "1_1") (pintype "passive"))
      (node (ref "CSH3") (pin "1") (pinfunction "1_1") (pintype "passive"))
      (node (ref "Cheetah") (pin "10") (pinfunction "10_10") (pintype "passive"))
      (node (ref "Cheetah") (pin "2") (pinfunction "2_2") (pintype "passive"))
      (node (ref "HILO1") (pin "3") (pinfunction "3_3") (pintype "passive"))
      (node (ref "HILO2") (pin "3") (pinfunction "3_3") (pintype "passive"))
      (node (ref "HILO3") (pin "3") (pinfunction "3_3") (pintype "passive"))
      (node (ref "MODE1") (pin "3") (pinfunction "3_3") (pintype "passive"))
      (node (ref "MODE2") (pin "3") (pinfunction "3_3") (pintype "passive"))
      (node (ref "MODE3") (pin "3") (pinfunction "3_3") (pintype "passive"))
      (node (ref "PWR") (pin "2") (pinfunction "K_2") (pintype "passive"))
      (node (ref "VGA1") (pin "17") (pinfunction "COMM_17") (pintype "power_in"))
      (node (ref "VGA1") (pin "20") (pinfunction "COMM_20") (pintype "power_in"))
      (node (ref "VGA2") (pin "17") (pinfunction "COMM_17") (pintype "power_in"))
      (node (ref "VGA2") (pin "20") (pinfunction "COMM_20") (pintype "power_in"))
      (node (ref "VGA3") (pin "17") (pinfunction "COMM_17") (pintype "power_in"))
      (node (ref "VGA3") (pin "20") (pinfunction "COMM_20") (pintype "power_in"))
      (node (ref "VR") (pin "2") (pinfunction "GND_2") (pintype "power_in"))
    )
    (net (code "30") (name "Net-(ADC1-VREF)") (class "Default")
      (node (ref "ADC1") (pin "3") (pinfunction "VREF_3") (pintype "power_in"))
      (node (ref "C1_1") (pin "2") (pinfunction "2_2") (pintype "passive"))
    )
    (net (code "31") (name "Net-(ADC2-VREF)") (class "Default")
      (node (ref "ADC2") (pin "3") (pinfunction "VREF_3") (pintype "power_in"))
      (node (ref "C1_2") (pin "2") (pinfunction "2_2") (pintype "passive"))
    )
    (net (code "32") (name "Net-(ADC3-VREF)") (class "Default")
      (node (ref "ADC3") (pin "3") (pinfunction "VREF_3") (pintype "power_in"))
      (node (ref "C1_3") (pin "2") (pinfunction "2_2") (pintype "passive"))
    )
    (net (code "33") (name "Net-(AUX-A)") (class "Default")
      (node (ref "AUX") (pin "1") (pinfunction "A_1") (pintype "passive"))
      (node (ref "R3") (pin "1") (pinfunction "1_1") (pintype "passive"))
    )
    (net (code "34") (name "Net-(Arduino-Pad1)") (class "Default")
      (node (ref "Arduino") (pin "1") (pinfunction "1_1") (pintype "passive"))
      (node (ref "RG_1") (pin "2") (pinfunction "2_2") (pintype "passive"))
    )
    (net (code "35") (name "Net-(Arduino-Pad10)") (class "Default")
      (node (ref "Arduino") (pin "10") (pinfunction "10_10") (pintype "passive"))
      (node (ref "RG_2") (pin "1") (pinfunction "1_1") (pintype "passive"))
    )
    (net (code "36") (name "Net-(Arduino-Pad15)") (class "Default")
      (node (ref "Arduino") (pin "15") (pinfunction "15_15") (pintype "passive"))
      (node (ref "RG_3") (pin "2") (pinfunction "2_2") (pintype "passive"))
    )
    (net (code "37") (name "Net-(CFB1-Pad1)") (class "Default")
      (node (ref "CFB1") (pin "1") (pinfunction "1_1") (pintype "passive"))
      (node (ref "RFB1") (pin "2") (pinfunction "2_2") (pintype "passive"))
    )
    (net (code "38") (name "Net-(CFB2-Pad1)") (class "Default")
      (node (ref "CFB2") (pin "1") (pinfunction "1_1") (pintype "passive"))
      (node (ref "RFB2") (pin "2") (pinfunction "2_2") (pintype "passive"))
    )
    (net (code "39") (name "Net-(CFB3-Pad1)") (class "Default")
      (node (ref "CFB3") (pin "1") (pinfunction "1_1") (pintype "passive"))
      (node (ref "RFB3") (pin "2") (pinfunction "2_2") (pintype "passive"))
    )
    (net (code "40") (name "Net-(CINH1-Pad2)") (class "Default")
      (node (ref "CINH1") (pin "2") (pinfunction "2_2") (pintype "passive"))
      (node (ref "L1_1") (pin "2") (pinfunction "2_2") (pintype "passive"))
    )
    (net (code "41") (name "Net-(CINH2-Pad2)") (class "Default")
      (node (ref "CINH2") (pin "2") (pinfunction "2_2") (pintype "passive"))
      (node (ref "L1_2") (pin "2") (pinfunction "2_2") (pintype "passive"))
    )
    (net (code "42") (name "Net-(CINH3-Pad2)") (class "Default")
      (node (ref "CINH3") (pin "2") (pinfunction "2_2") (pintype "passive"))
      (node (ref "L1_3") (pin "2") (pinfunction "2_2") (pintype "passive"))
    )
    (net (code "43") (name "Net-(CLK-A)") (class "Default")
      (node (ref "CLK") (pin "1") (pinfunction "A_1") (pintype "passive"))
      (node (ref "R2") (pin "1") (pinfunction "1_1") (pintype "passive"))
    )
    (net (code "44") (name "Net-(PWR-A)") (class "Default")
      (node (ref "PWR") (pin "1") (pinfunction "A_1") (pintype "passive"))
      (node (ref "R1") (pin "1") (pinfunction "1_1") (pintype "passive"))
    )
    (net (code "45") (name "Net-(VGA1-HILO)") (class "Default")
      (node (ref "HILO1") (pin "2") (pinfunction "2_2") (pintype "passive"))
      (node (ref "VGA1") (pin "13") (pinfunction "HILO_13") (pintype "power_in"))
    )
    (net (code "46") (name "Net-(VGA1-INH)") (class "Default")
      (node (ref "CFB1") (pin "2") (pinfunction "2_2") (pintype "passive"))
      (node (ref "CINH1") (pin "1") (pinfunction "1_1") (pintype "passive"))
      (node (ref "CSH1") (pin "2") (pinfunction "2_2") (pintype "passive"))
      (node (ref "VGA1") (pin "2") (pinfunction "INH_2") (pintype "power_in"))
    )
    (net (code "47") (name "Net-(VGA1-LMD)") (class "Default")
      (node (ref "CLMD1") (pin "2") (pinfunction "2_2") (pintype "passive"))
      (node (ref "VGA1") (pin "1") (pinfunction "LMD_1") (pintype "power_in"))
    )
    (net (code "48") (name "Net-(VGA1-LON)") (class "Default")
      (node (ref "C16_1") (pin "2") (pinfunction "2_2") (pintype "passive"))
      (node (ref "RFB1") (pin "1") (pinfunction "1_1") (pintype "passive"))
      (node (ref "VGA1") (pin "4") (pinfunction "LON_4") (pintype "power_in"))
    )
    (net (code "49") (name "Net-(VGA1-LOP)") (class "Default")
      (node (ref "C14_1") (pin "2") (pinfunction "2_2") (pintype "passive"))
      (node (ref "VGA1") (pin "5") (pinfunction "LOP_5") (pintype "power_in"))
    )
    (net (code "50") (name "Net-(VGA1-MODE)") (class "Default")
      (node (ref "MODE1") (pin "2") (pinfunction "2_2") (pintype "passive"))
      (node (ref "VGA1") (pin "9") (pinfunction "MODE_9") (pintype "power_in"))
    )
    (net (code "51") (name "Net-(VGA1-RCLMP)") (class "Default")
      (node (ref "C17_1") (pin "2") (pinfunction "2_2") (pintype "passive"))
      (node (ref "VGA1") (pin "12") (pinfunction "RCLMP_12") (pintype "power_in"))
    )
    (net (code "52") (name "Net-(VGA1-VIN)") (class "Default")
      (node (ref "C16_1") (pin "1") (pinfunction "1_1") (pintype "passive"))
      (node (ref "VGA1") (pin "8") (pinfunction "VIN_8") (pintype "power_in"))
    )
    (net (code "53") (name "Net-(VGA1-VIP)") (class "Default")
      (node (ref "C14_1") (pin "1") (pinfunction "1_1") (pintype "passive"))
      (node (ref "VGA1") (pin "7") (pinfunction "VIP_7") (pintype "power_in"))
    )
    (net (code "54") (name "Net-(VGA1-VOH)") (class "Default")
      (node (ref "L4_1") (pin "2") (pinfunction "2_2") (pintype "passive"))
      (node (ref "R43_1") (pin "1") (pinfunction "1_1") (pintype "passive"))
      (node (ref "VGA1") (pin "15") (pinfunction "VOH_15") (pintype "power_in"))
    )
    (net (code "55") (name "Net-(VGA1-VOL)") (class "Default")
      (node (ref "L3_1") (pin "2") (pinfunction "2_2") (pintype "passive"))
      (node (ref "R44_1") (pin "1") (pinfunction "1_1") (pintype "passive"))
      (node (ref "VGA1") (pin "16") (pinfunction "VOL_16") (pintype "power_in"))
    )
    (net (code "56") (name "Net-(VGA1-VPOS)") (class "Default")
      (node (ref "C32_1") (pin "2") (pinfunction "2_2") (pintype "passive"))
      (node (ref "L5_1") (pin "2") (pinfunction "2_2") (pintype "passive"))
      (node (ref "VGA1") (pin "14") (pinfunction "VPOS_14") (pintype "power_in"))
    )
    (net (code "57") (name "Net-(VGA1-VPSL)") (class "Default")
      (node (ref "C6_1") (pin "2") (pinfunction "2_2") (pintype "passive"))
      (node (ref "L2_1") (pin "2") (pinfunction "2_2") (pintype "passive"))
      (node (ref "VGA1") (pin "3") (pinfunction "VPSL_3") (pintype "power_in"))
    )
    (net (code "58") (name "Net-(VGA2-HILO)") (class "Default")
      (node (ref "HILO2") (pin "2") (pinfunction "2_2") (pintype "passive"))
      (node (ref "VGA2") (pin "13") (pinfunction "HILO_13") (pintype "power_in"))
    )
    (net (code "59") (name "Net-(VGA2-INH)") (class "Default")
      (node (ref "CFB2") (pin "2") (pinfunction "2_2") (pintype "passive"))
      (node (ref "CINH2") (pin "1") (pinfunction "1_1") (pintype "passive"))
      (node (ref "CSH2") (pin "2") (pinfunction "2_2") (pintype "passive"))
      (node (ref "VGA2") (pin "2") (pinfunction "INH_2") (pintype "power_in"))
    )
    (net (code "60") (name "Net-(VGA2-LMD)") (class "Default")
      (node (ref "CLMD2") (pin "2") (pinfunction "2_2") (pintype "passive"))
      (node (ref "VGA2") (pin "1") (pinfunction "LMD_1") (pintype "power_in"))
    )
    (net (code "61") (name "Net-(VGA2-LON)") (class "Default")
      (node (ref "C16_2") (pin "2") (pinfunction "2_2") (pintype "passive"))
      (node (ref "RFB2") (pin "1") (pinfunction "1_1") (pintype "passive"))
      (node (ref "VGA2") (pin "4") (pinfunction "LON_4") (pintype "power_in"))
    )
    (net (code "62") (name "Net-(VGA2-LOP)") (class "Default")
      (node (ref "C14_2") (pin "2") (pinfunction "2_2") (pintype "passive"))
      (node (ref "VGA2") (pin "5") (pinfunction "LOP_5") (pintype "power_in"))
    )
    (net (code "63") (name "Net-(VGA2-MODE)") (class "Default")
      (node (ref "MODE2") (pin "2") (pinfunction "2_2") (pintype "passive"))
      (node (ref "VGA2") (pin "9") (pinfunction "MODE_9") (pintype "power_in"))
    )
    (net (code "64") (name "Net-(VGA2-RCLMP)") (class "Default")
      (node (ref "C17_2") (pin "2") (pinfunction "2_2") (pintype "passive"))
      (node (ref "VGA2") (pin "12") (pinfunction "RCLMP_12") (pintype "power_in"))
    )
    (net (code "65") (name "Net-(VGA2-VIN)") (class "Default")
      (node (ref "C16_2") (pin "1") (pinfunction "1_1") (pintype "passive"))
      (node (ref "VGA2") (pin "8") (pinfunction "VIN_8") (pintype "power_in"))
    )
    (net (code "66") (name "Net-(VGA2-VIP)") (class "Default")
      (node (ref "C14_2") (pin "1") (pinfunction "1_1") (pintype "passive"))
      (node (ref "VGA2") (pin "7") (pinfunction "VIP_7") (pintype "power_in"))
    )
    (net (code "67") (name "Net-(VGA2-VOH)") (class "Default")
      (node (ref "L4_2") (pin "2") (pinfunction "2_2") (pintype "passive"))
      (node (ref "R43_2") (pin "1") (pinfunction "1_1") (pintype "passive"))
      (node (ref "VGA2") (pin "15") (pinfunction "VOH_15") (pintype "power_in"))
    )
    (net (code "68") (name "Net-(VGA2-VOL)") (class "Default")
      (node (ref "L3_2") (pin "2") (pinfunction "2_2") (pintype "passive"))
      (node (ref "R44_2") (pin "1") (pinfunction "1_1") (pintype "passive"))
      (node (ref "VGA2") (pin "16") (pinfunction "VOL_16") (pintype "power_in"))
    )
    (net (code "69") (name "Net-(VGA2-VPOS)") (class "Default")
      (node (ref "C32_2") (pin "2") (pinfunction "2_2") (pintype "passive"))
      (node (ref "L5_2") (pin "2") (pinfunction "2_2") (pintype "passive"))
      (node (ref "VGA2") (pin "14") (pinfunction "VPOS_14") (pintype "power_in"))
    )
    (net (code "70") (name "Net-(VGA2-VPSL)") (class "Default")
      (node (ref "C6_2") (pin "2") (pinfunction "2_2") (pintype "passive"))
      (node (ref "L2_2") (pin "2") (pinfunction "2_2") (pintype "passive"))
      (node (ref "VGA2") (pin "3") (pinfunction "VPSL_3") (pintype "power_in"))
    )
    (net (code "71") (name "Net-(VGA3-HILO)") (class "Default")
      (node (ref "HILO3") (pin "2") (pinfunction "2_2") (pintype "passive"))
      (node (ref "VGA3") (pin "13") (pinfunction "HILO_13") (pintype "power_in"))
    )
    (net (code "72") (name "Net-(VGA3-INH)") (class "Default")
      (node (ref "CFB3") (pin "2") (pinfunction "2_2") (pintype "passive"))
      (node (ref "CINH3") (pin "1") (pinfunction "1_1") (pintype "passive"))
      (node (ref "CSH3") (pin "2") (pinfunction "2_2") (pintype "passive"))
      (node (ref "VGA3") (pin "2") (pinfunction "INH_2") (pintype "power_in"))
    )
    (net (code "73") (name "Net-(VGA3-LMD)") (class "Default")
      (node (ref "CLMD3") (pin "2") (pinfunction "2_2") (pintype "passive"))
      (node (ref "VGA3") (pin "1") (pinfunction "LMD_1") (pintype "power_in"))
    )
    (net (code "74") (name "Net-(VGA3-LON)") (class "Default")
      (node (ref "C16_3") (pin "2") (pinfunction "2_2") (pintype "passive"))
      (node (ref "RFB3") (pin "1") (pinfunction "1_1") (pintype "passive"))
      (node (ref "VGA3") (pin "4") (pinfunction "LON_4") (pintype "power_in"))
    )
    (net (code "75") (name "Net-(VGA3-LOP)") (class "Default")
      (node (ref "C14_3") (pin "2") (pinfunction "2_2") (pintype "passive"))
      (node (ref "VGA3") (pin "5") (pinfunction "LOP_5") (pintype "power_in"))
    )
    (net (code "76") (name "Net-(VGA3-MODE)") (class "Default")
      (node (ref "MODE3") (pin "2") (pinfunction "2_2") (pintype "passive"))
      (node (ref "VGA3") (pin "9") (pinfunction "MODE_9") (pintype "power_in"))
    )
    (net (code "77") (name "Net-(VGA3-RCLMP)") (class "Default")
      (node (ref "C17_3") (pin "2") (pinfunction "2_2") (pintype "passive"))
      (node (ref "VGA3") (pin "12") (pinfunction "RCLMP_12") (pintype "power_in"))
    )
    (net (code "78") (name "Net-(VGA3-VIN)") (class "Default")
      (node (ref "C16_3") (pin "1") (pinfunction "1_1") (pintype "passive"))
      (node (ref "VGA3") (pin "8") (pinfunction "VIN_8") (pintype "power_in"))
    )
    (net (code "79") (name "Net-(VGA3-VIP)") (class "Default")
      (node (ref "C14_3") (pin "1") (pinfunction "1_1") (pintype "passive"))
      (node (ref "VGA3") (pin "7") (pinfunction "VIP_7") (pintype "power_in"))
    )
    (net (code "80") (name "Net-(VGA3-VOH)") (class "Default")
      (node (ref "L4_3") (pin "2") (pinfunction "2_2") (pintype "passive"))
      (node (ref "R43_3") (pin "1") (pinfunction "1_1") (pintype "passive"))
      (node (ref "VGA3") (pin "15") (pinfunction "VOH_15") (pintype "power_in"))
    )
    (net (code "81") (name "Net-(VGA3-VOL)") (class "Default")
      (node (ref "L3_3") (pin "2") (pinfunction "2_2") (pintype "passive"))
      (node (ref "R44_3") (pin "1") (pinfunction "1_1") (pintype "passive"))
      (node (ref "VGA3") (pin "16") (pinfunction "VOL_16") (pintype "power_in"))
    )
    (net (code "82") (name "Net-(VGA3-VPOS)") (class "Default")
      (node (ref "C32_3") (pin "2") (pinfunction "2_2") (pintype "passive"))
      (node (ref "L5_3") (pin "2") (pinfunction "2_2") (pintype "passive"))
      (node (ref "VGA3") (pin "14") (pinfunction "VPOS_14") (pintype "power_in"))
    )
    (net (code "83") (name "Net-(VGA3-VPSL)") (class "Default")
      (node (ref "C6_3") (pin "2") (pinfunction "2_2") (pintype "passive"))
      (node (ref "L2_3") (pin "2") (pinfunction "2_2") (pintype "passive"))
      (node (ref "VGA3") (pin "3") (pinfunction "VPSL_3") (pintype "power_in"))
    )
    (net (code "84") (name "Net-(VR-Bypass)") (class "Default")
      (node (ref "C3") (pin "2") (pinfunction "2_2") (pintype "passive"))
      (node (ref "VR") (pin "4") (pinfunction "Bypass_4") (pintype "power_in"))
    )
  )
)
